# iotpanel.net
KiCad netlist of a schematic drawn in EAGLE
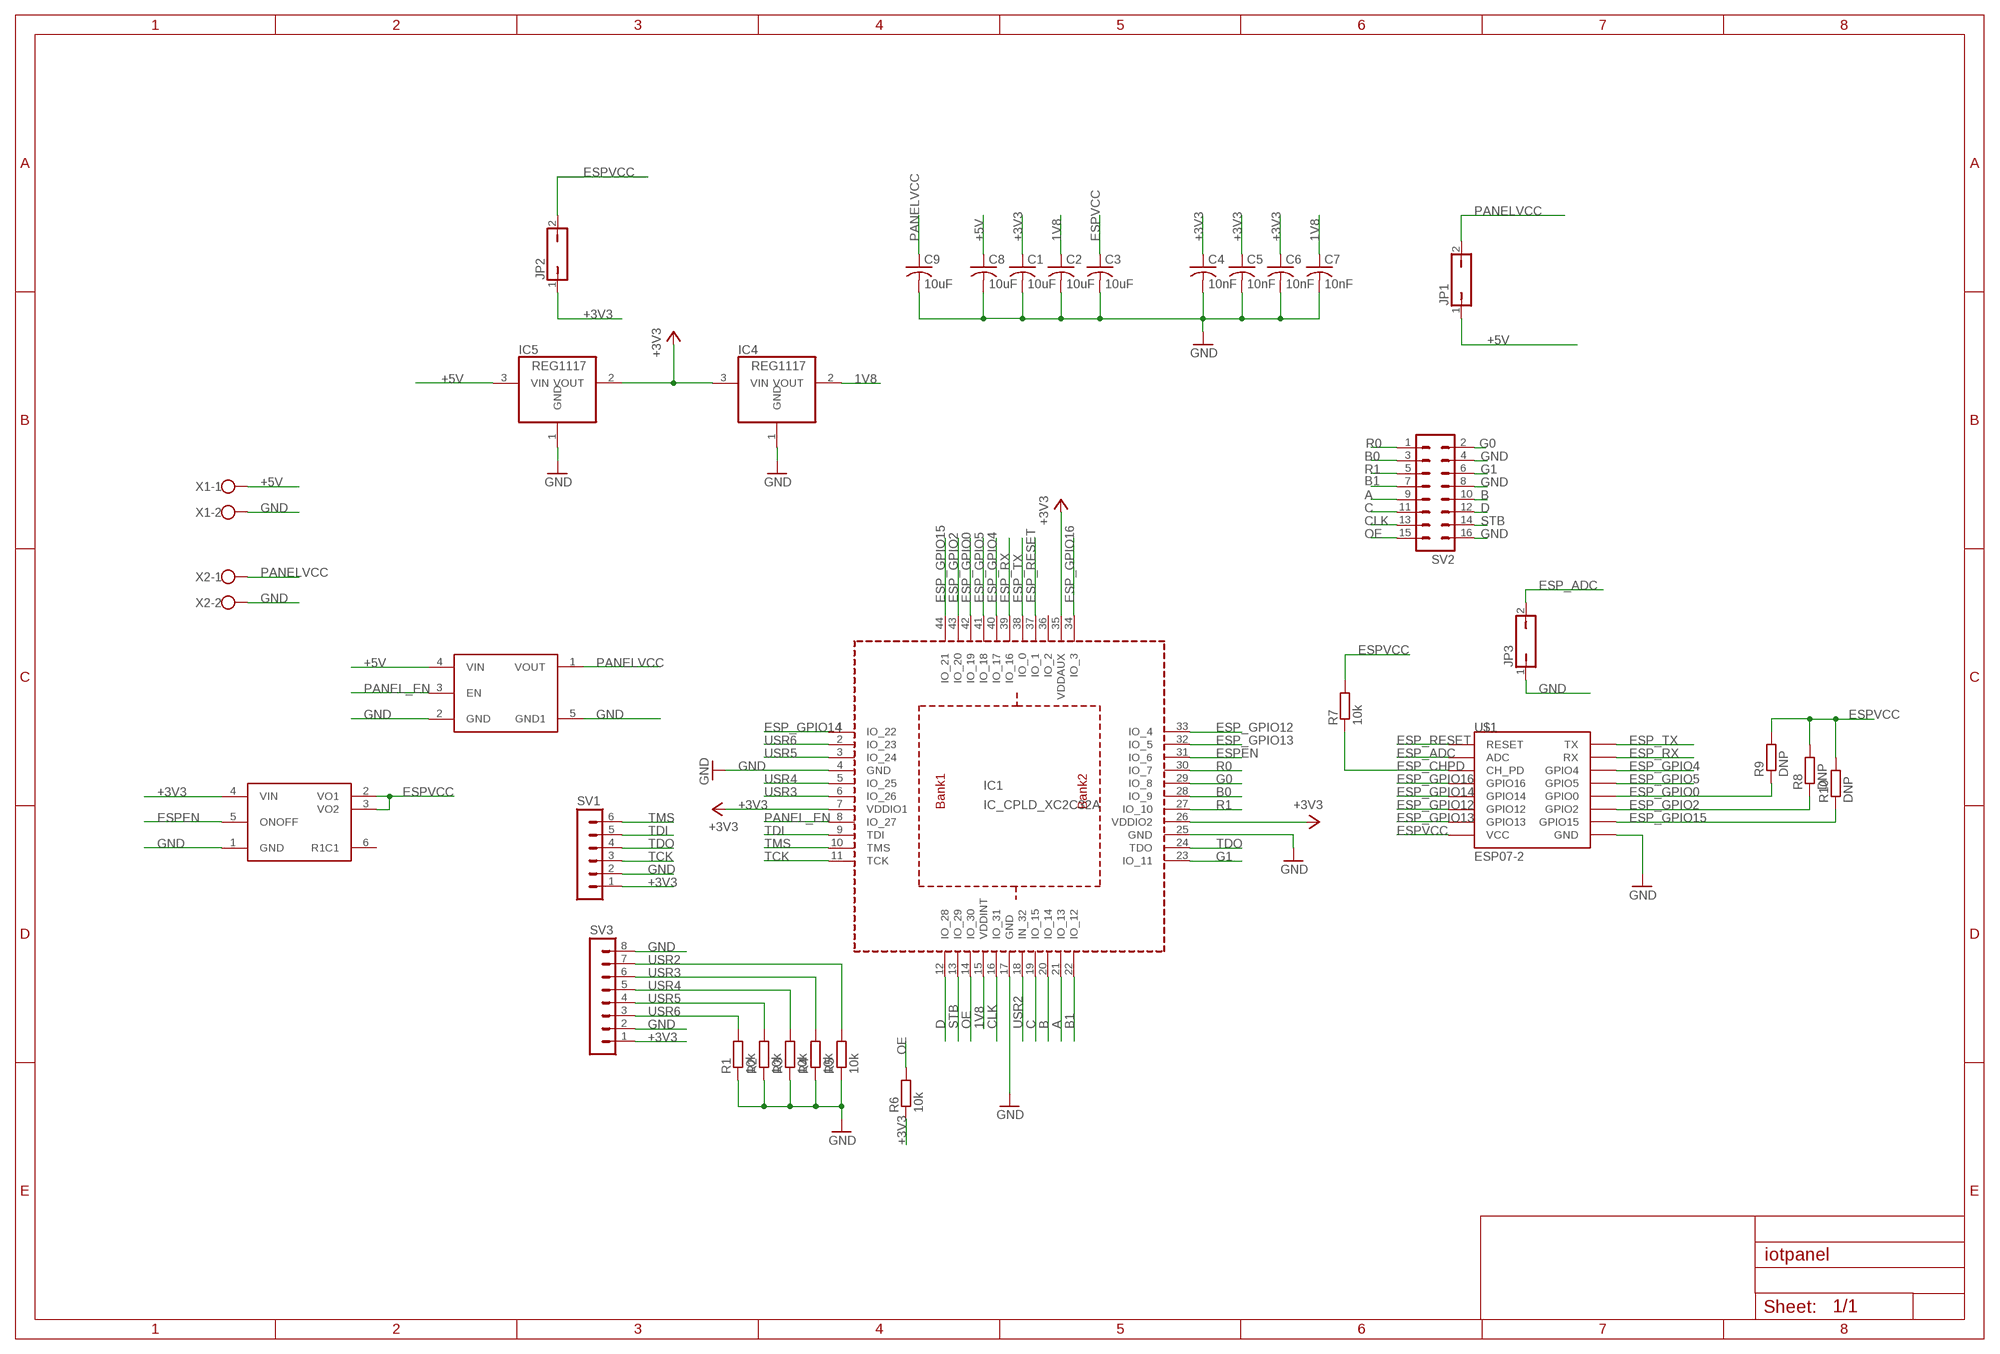
[diagram p0: schematic, sheet 1]

(export (version "E")
  (design (tool "Eeschema 10.0.6"))
  (components
    (comp (ref "C1")
      (value "10uF")
      (footprint "eagle-import:CAPC0805")
      (libsource (lib "eagle-import") (part "CAPACITOR_-0805"))
    )
    (comp (ref "C2")
      (value "10uF")
      (footprint "eagle-import:CAPC0805")
      (libsource (lib "eagle-import") (part "CAPACITOR_-0805"))
    )
    (comp (ref "C3")
      (value "10uF")
      (footprint "eagle-import:CAPC0805")
      (libsource (lib "eagle-import") (part "CAPACITOR_-0805"))
    )
    (comp (ref "C4")
      (value "10nF")
      (footprint "eagle-import:CAPC0805")
      (libsource (lib "eagle-import") (part "CAPACITOR_-0805"))
    )
    (comp (ref "C5")
      (value "10nF")
      (footprint "eagle-import:CAPC0805")
      (libsource (lib "eagle-import") (part "CAPACITOR_-0805"))
    )
    (comp (ref "C6")
      (value "10nF")
      (footprint "eagle-import:CAPC0805")
      (libsource (lib "eagle-import") (part "CAPACITOR_-0805"))
    )
    (comp (ref "C7")
      (value "10nF")
      (footprint "eagle-import:CAPC0805")
      (libsource (lib "eagle-import") (part "CAPACITOR_-0805"))
    )
    (comp (ref "C8")
      (value "10uF")
      (footprint "eagle-import:CAPC0805")
      (libsource (lib "eagle-import") (part "CAPACITOR_-0805"))
    )
    (comp (ref "C9")
      (value "10uF")
      (footprint "eagle-import:CAPC0805")
      (libsource (lib "eagle-import") (part "CAPACITOR_-0805"))
    )
    (comp (ref "IC1")
      (value "IC_CPLD_XC2C32A")
      (footprint "eagle-import:VQ-44")
      (libsource (lib "eagle-import") (part "IC_CPLD_XC2C32A"))
    )
    (comp (ref "IC4")
      (value "REG1117")
      (footprint "eagle-import:SOT223")
      (libsource (lib "eagle-import") (part "REG1117"))
    )
    (comp (ref "IC5")
      (value "REG1117")
      (footprint "eagle-import:SOT223")
      (libsource (lib "eagle-import") (part "REG1117"))
    )
    (comp (ref "JP1")
      (value "JP1Q")
      (footprint "eagle-import:JP1")
      (libsource (lib "eagle-import") (part "JP1Q"))
    )
    (comp (ref "JP2")
      (value "JP1Q")
      (footprint "eagle-import:JP1")
      (libsource (lib "eagle-import") (part "JP1Q"))
    )
    (comp (ref "JP3")
      (value "JP1Q")
      (footprint "eagle-import:JP1")
      (libsource (lib "eagle-import") (part "JP1Q"))
    )
    (comp (ref "R1")
      (value "10k")
      (footprint "eagle-import:R0805")
      (libsource (lib "eagle-import") (part "R-EU_R0805"))
    )
    (comp (ref "R2")
      (value "10k")
      (footprint "eagle-import:R0805")
      (libsource (lib "eagle-import") (part "R-EU_R0805"))
    )
    (comp (ref "R3")
      (value "10k")
      (footprint "eagle-import:R0805")
      (libsource (lib "eagle-import") (part "R-EU_R0805"))
    )
    (comp (ref "R4")
      (value "10k")
      (footprint "eagle-import:R0805")
      (libsource (lib "eagle-import") (part "R-EU_R0805"))
    )
    (comp (ref "R5")
      (value "10k")
      (footprint "eagle-import:R0805")
      (libsource (lib "eagle-import") (part "R-EU_R0805"))
    )
    (comp (ref "R6")
      (value "10k")
      (footprint "eagle-import:R0805")
      (libsource (lib "eagle-import") (part "R-EU_R0805"))
    )
    (comp (ref "R7")
      (value "10k")
      (footprint "eagle-import:R0805")
      (libsource (lib "eagle-import") (part "R-EU_R0805"))
    )
    (comp (ref "R8")
      (value "DNP")
      (footprint "eagle-import:R0805")
      (libsource (lib "eagle-import") (part "R-EU_R0805"))
    )
    (comp (ref "R9")
      (value "DNP")
      (footprint "eagle-import:R0805")
      (libsource (lib "eagle-import") (part "R-EU_R0805"))
    )
    (comp (ref "R10")
      (value "DNP")
      (footprint "eagle-import:R0805")
      (libsource (lib "eagle-import") (part "R-EU_R0805"))
    )
    (comp (ref "SV1")
      (value "MA06-1")
      (footprint "eagle-import:MA06-1")
      (libsource (lib "eagle-import") (part "MA06-1"))
    )
    (comp (ref "SV2")
      (value "ML16")
      (footprint "eagle-import:ML16")
      (fields (field (name "PARTNO") "PRPC004DAAN-RC"))
      (libsource (lib "eagle-import") (part "ML16"))
    )
    (comp (ref "SV3")
      (value "MA08-1")
      (footprint "eagle-import:MA08-1")
      (libsource (lib "eagle-import") (part "MA08-1"))
    )
    (comp (ref "U$1")
      (value "ESP07-2")
      (footprint "eagle-import:ESP07-2")
      (libsource (lib "eagle-import") (part "ESP07-2"))
    )
    (comp (ref "U$2")
      (value "MIC9406XBC6")
      (footprint "eagle-import:SC70-6L")
      (libsource (lib "eagle-import") (part "MIC9406XBC6"))
    )
    (comp (ref "U$3")
      (value "SI1867DL")
      (footprint "eagle-import:SC70-6L")
      (libsource (lib "eagle-import") (part "SI1867DL"))
    )
    (comp (ref "X1")
      (value "W237-102")
      (footprint "eagle-import:W237-102")
      (fields (field (name "MPN") "237-102"))
      (libsource (lib "eagle-import") (part "W237-102"))
    )
    (comp (ref "X2")
      (value "W237-102")
      (footprint "eagle-import:W237-102")
      (fields (field (name "MPN") "237-102"))
      (libsource (lib "eagle-import") (part "W237-102"))
    )
  )
  (nets
    (net (code "1") (name "+3V3") (class "Default")
      (node (ref "C1") (pin "1") (pinfunction "1_1") (pintype "passive"))
      (node (ref "C4") (pin "1") (pinfunction "1_1") (pintype "passive"))
      (node (ref "C5") (pin "1") (pinfunction "1_1") (pintype "passive"))
      (node (ref "C6") (pin "1") (pinfunction "1_1") (pintype "passive"))
      (node (ref "IC1") (pin "26") (pinfunction "VDDIO2_26") (pintype "power_in"))
      (node (ref "IC1") (pin "35") (pinfunction "VDDAUX_35") (pintype "power_in"))
      (node (ref "IC1") (pin "7") (pinfunction "VDDIO1_7") (pintype "power_in"))
      (node (ref "IC4") (pin "3") (pinfunction "VIN_3") (pintype "input"))
      (node (ref "IC5") (pin "2") (pinfunction "VOUT_2") (pintype "output"))
      (node (ref "JP2") (pin "1") (pinfunction "1_1") (pintype "passive"))
      (node (ref "R6") (pin "1") (pinfunction "1_1") (pintype "passive"))
      (node (ref "SV1") (pin "1") (pinfunction "1_1") (pintype "passive"))
      (node (ref "SV3") (pin "1") (pinfunction "1_1") (pintype "passive"))
      (node (ref "U$3") (pin "4") (pinfunction "VIN_4") (pintype "power_in"))
    )
    (net (code "2") (name "/+5V") (class "Default")
      (node (ref "C8") (pin "1") (pinfunction "1_1") (pintype "passive"))
      (node (ref "IC5") (pin "3") (pinfunction "VIN_3") (pintype "input"))
      (node (ref "JP1") (pin "1") (pinfunction "1_1") (pintype "passive"))
      (node (ref "U$2") (pin "4") (pinfunction "VIN_4") (pintype "power_in"))
      (node (ref "X1") (pin "1") (pinfunction "KL_1") (pintype "passive"))
    )
    (net (code "3") (name "/1V8") (class "Default")
      (node (ref "C2") (pin "1") (pinfunction "1_1") (pintype "passive"))
      (node (ref "C7") (pin "1") (pinfunction "1_1") (pintype "passive"))
      (node (ref "IC1") (pin "15") (pinfunction "VDDINT_15") (pintype "power_in"))
      (node (ref "IC4") (pin "2") (pinfunction "VOUT_2") (pintype "output"))
    )
    (net (code "4") (name "/A") (class "Default")
      (node (ref "IC1") (pin "21") (pinfunction "IO_13_21") (pintype "bidirectional"))
      (node (ref "SV2") (pin "9") (pinfunction "9_9") (pintype "passive"))
    )
    (net (code "5") (name "/B") (class "Default")
      (node (ref "IC1") (pin "20") (pinfunction "IO_14_20") (pintype "bidirectional"))
      (node (ref "SV2") (pin "10") (pinfunction "10_10") (pintype "passive"))
    )
    (net (code "6") (name "/B0") (class "Default")
      (node (ref "IC1") (pin "28") (pinfunction "IO_9_28") (pintype "bidirectional"))
      (node (ref "SV2") (pin "3") (pinfunction "3_3") (pintype "passive"))
    )
    (net (code "7") (name "/B1") (class "Default")
      (node (ref "IC1") (pin "22") (pinfunction "IO_12_22") (pintype "bidirectional"))
      (node (ref "SV2") (pin "7") (pinfunction "7_7") (pintype "passive"))
    )
    (net (code "8") (name "/C") (class "Default")
      (node (ref "IC1") (pin "19") (pinfunction "IO_15_19") (pintype "bidirectional"))
      (node (ref "SV2") (pin "11") (pinfunction "11_11") (pintype "passive"))
    )
    (net (code "9") (name "/CLK") (class "Default")
      (node (ref "IC1") (pin "16") (pinfunction "IO_31_16") (pintype "bidirectional"))
      (node (ref "SV2") (pin "13") (pinfunction "13_13") (pintype "passive"))
    )
    (net (code "10") (name "/D") (class "Default")
      (node (ref "IC1") (pin "12") (pinfunction "IO_28_12") (pintype "bidirectional"))
      (node (ref "SV2") (pin "12") (pinfunction "12_12") (pintype "passive"))
    )
    (net (code "11") (name "/ESPEN") (class "Default")
      (node (ref "IC1") (pin "31") (pinfunction "IO_6_31") (pintype "bidirectional"))
      (node (ref "U$3") (pin "5") (pinfunction "ONOFF_5") (pintype "input"))
    )
    (net (code "12") (name "/ESPVCC") (class "Default")
      (node (ref "C3") (pin "1") (pinfunction "1_1") (pintype "passive"))
      (node (ref "JP2") (pin "2") (pinfunction "2_2") (pintype "passive"))
      (node (ref "R10") (pin "2") (pinfunction "2_2") (pintype "passive"))
      (node (ref "R7") (pin "2") (pinfunction "2_2") (pintype "passive"))
      (node (ref "R8") (pin "2") (pinfunction "2_2") (pintype "passive"))
      (node (ref "R9") (pin "2") (pinfunction "2_2") (pintype "passive"))
      (node (ref "U$1") (pin "VCC") (pinfunction "VCC_VCC") (pintype "bidirectional"))
      (node (ref "U$3") (pin "2") (pinfunction "VO1_2") (pintype "power_in"))
      (node (ref "U$3") (pin "3") (pinfunction "VO2_3") (pintype "power_in"))
    )
    (net (code "13") (name "/ESP_ADC") (class "Default")
      (node (ref "JP3") (pin "2") (pinfunction "2_2") (pintype "passive"))
      (node (ref "U$1") (pin "ADC") (pinfunction "ADC_ADC") (pintype "bidirectional"))
    )
    (net (code "14") (name "/ESP_CHPD") (class "Default")
      (node (ref "R7") (pin "1") (pinfunction "1_1") (pintype "passive"))
      (node (ref "U$1") (pin "CH_PD") (pinfunction "CH_PD_CH_PD") (pintype "bidirectional"))
    )
    (net (code "15") (name "/ESP_GPIO0") (class "Default")
      (node (ref "IC1") (pin "42") (pinfunction "IO_19_42") (pintype "bidirectional"))
      (node (ref "R9") (pin "1") (pinfunction "1_1") (pintype "passive"))
      (node (ref "U$1") (pin "GPIO0") (pinfunction "GPIO0_GPIO0") (pintype "bidirectional"))
    )
    (net (code "16") (name "/ESP_GPIO2") (class "Default")
      (node (ref "IC1") (pin "43") (pinfunction "IO_20_43") (pintype "bidirectional"))
      (node (ref "R8") (pin "1") (pinfunction "1_1") (pintype "passive"))
      (node (ref "U$1") (pin "GPIO2") (pinfunction "GPIO2_GPIO2") (pintype "bidirectional"))
    )
    (net (code "17") (name "/ESP_GPIO4") (class "Default")
      (node (ref "IC1") (pin "40") (pinfunction "IO_17_40") (pintype "bidirectional"))
      (node (ref "U$1") (pin "GPIO4") (pinfunction "GPIO4_GPIO4") (pintype "bidirectional"))
    )
    (net (code "18") (name "/ESP_GPIO5") (class "Default")
      (node (ref "IC1") (pin "41") (pinfunction "IO_18_41") (pintype "bidirectional"))
      (node (ref "U$1") (pin "GPIO5") (pinfunction "GPIO5_GPIO5") (pintype "bidirectional"))
    )
    (net (code "19") (name "/ESP_GPIO12") (class "Default")
      (node (ref "IC1") (pin "33") (pinfunction "IO_4_33") (pintype "bidirectional"))
      (node (ref "U$1") (pin "GPIO12") (pinfunction "GPIO12_GPIO12") (pintype "bidirectional"))
    )
    (net (code "20") (name "/ESP_GPIO13") (class "Default")
      (node (ref "IC1") (pin "32") (pinfunction "IO_5_32") (pintype "bidirectional"))
      (node (ref "U$1") (pin "GPIO13") (pinfunction "GPIO13_GPIO13") (pintype "bidirectional"))
    )
    (net (code "21") (name "/ESP_GPIO14") (class "Default")
      (node (ref "IC1") (pin "1") (pinfunction "IO_22_1") (pintype "bidirectional"))
      (node (ref "U$1") (pin "GPIO14") (pinfunction "GPIO14_GPIO14") (pintype "bidirectional"))
    )
    (net (code "22") (name "/ESP_GPIO15") (class "Default")
      (node (ref "IC1") (pin "44") (pinfunction "IO_21_44") (pintype "bidirectional"))
      (node (ref "R10") (pin "1") (pinfunction "1_1") (pintype "passive"))
      (node (ref "U$1") (pin "GPIO15") (pinfunction "GPIO15_GPIO15") (pintype "bidirectional"))
    )
    (net (code "23") (name "/ESP_GPIO16") (class "Default")
      (node (ref "IC1") (pin "34") (pinfunction "IO_3_34") (pintype "bidirectional"))
      (node (ref "U$1") (pin "GPIO16") (pinfunction "GPIO16_GPIO16") (pintype "bidirectional"))
    )
    (net (code "24") (name "/ESP_RESET") (class "Default")
      (node (ref "IC1") (pin "37") (pinfunction "IO_1_37") (pintype "bidirectional"))
      (node (ref "U$1") (pin "REST") (pinfunction "RESET_REST") (pintype "bidirectional"))
    )
    (net (code "25") (name "/ESP_RX") (class "Default")
      (node (ref "IC1") (pin "39") (pinfunction "IO_16_39") (pintype "bidirectional"))
      (node (ref "U$1") (pin "RX") (pinfunction "RX_RX") (pintype "bidirectional"))
    )
    (net (code "26") (name "/ESP_TX") (class "Default")
      (node (ref "IC1") (pin "38") (pinfunction "IO_0_38") (pintype "bidirectional"))
      (node (ref "U$1") (pin "TX") (pinfunction "TX_TX") (pintype "bidirectional"))
    )
    (net (code "27") (name "/G0") (class "Default")
      (node (ref "IC1") (pin "29") (pinfunction "IO_8_29") (pintype "bidirectional"))
      (node (ref "SV2") (pin "2") (pinfunction "2_2") (pintype "passive"))
    )
    (net (code "28") (name "/G1") (class "Default")
      (node (ref "IC1") (pin "23") (pinfunction "IO_11_23") (pintype "bidirectional"))
      (node (ref "SV2") (pin "6") (pinfunction "6_6") (pintype "passive"))
    )
    (net (code "29") (name "/OE") (class "Default")
      (node (ref "IC1") (pin "14") (pinfunction "IO_30_14") (pintype "bidirectional"))
      (node (ref "R6") (pin "2") (pinfunction "2_2") (pintype "passive"))
      (node (ref "SV2") (pin "15") (pinfunction "15_15") (pintype "passive"))
    )
    (net (code "30") (name "/PANELVCC") (class "Default")
      (node (ref "C9") (pin "1") (pinfunction "1_1") (pintype "passive"))
      (node (ref "JP1") (pin "2") (pinfunction "2_2") (pintype "passive"))
      (node (ref "U$2") (pin "1") (pinfunction "VOUT_1") (pintype "power_in"))
      (node (ref "X2") (pin "1") (pinfunction "KL_1") (pintype "passive"))
    )
    (net (code "31") (name "/PANEL_EN") (class "Default")
      (node (ref "IC1") (pin "8") (pinfunction "IO_27_8") (pintype "bidirectional"))
      (node (ref "U$2") (pin "3") (pinfunction "EN_3") (pintype "input"))
    )
    (net (code "32") (name "/R0") (class "Default")
      (node (ref "IC1") (pin "30") (pinfunction "IO_7_30") (pintype "bidirectional"))
      (node (ref "SV2") (pin "1") (pinfunction "1_1") (pintype "passive"))
    )
    (net (code "33") (name "/R1") (class "Default")
      (node (ref "IC1") (pin "27") (pinfunction "IO_10_27") (pintype "bidirectional"))
      (node (ref "SV2") (pin "5") (pinfunction "5_5") (pintype "passive"))
    )
    (net (code "34") (name "/STB") (class "Default")
      (node (ref "IC1") (pin "13") (pinfunction "IO_29_13") (pintype "bidirectional"))
      (node (ref "SV2") (pin "14") (pinfunction "14_14") (pintype "passive"))
    )
    (net (code "35") (name "/TCK") (class "Default")
      (node (ref "IC1") (pin "11") (pinfunction "TCK_11") (pintype "input"))
      (node (ref "SV1") (pin "3") (pinfunction "3_3") (pintype "passive"))
    )
    (net (code "36") (name "/TDI") (class "Default")
      (node (ref "IC1") (pin "9") (pinfunction "TDI_9") (pintype "input"))
      (node (ref "SV1") (pin "5") (pinfunction "5_5") (pintype "passive"))
    )
    (net (code "37") (name "/TDO") (class "Default")
      (node (ref "IC1") (pin "24") (pinfunction "TDO_24") (pintype "output"))
      (node (ref "SV1") (pin "4") (pinfunction "4_4") (pintype "passive"))
    )
    (net (code "38") (name "/TMS") (class "Default")
      (node (ref "IC1") (pin "10") (pinfunction "TMS_10") (pintype "input"))
      (node (ref "SV1") (pin "6") (pinfunction "6_6") (pintype "passive"))
    )
    (net (code "39") (name "/USR2") (class "Default")
      (node (ref "IC1") (pin "18") (pinfunction "IN_32_18") (pintype "input"))
      (node (ref "R5") (pin "2") (pinfunction "2_2") (pintype "passive"))
      (node (ref "SV3") (pin "7") (pinfunction "7_7") (pintype "passive"))
    )
    (net (code "40") (name "/USR3") (class "Default")
      (node (ref "IC1") (pin "6") (pinfunction "IO_26_6") (pintype "bidirectional"))
      (node (ref "R4") (pin "2") (pinfunction "2_2") (pintype "passive"))
      (node (ref "SV3") (pin "6") (pinfunction "6_6") (pintype "passive"))
    )
    (net (code "41") (name "/USR4") (class "Default")
      (node (ref "IC1") (pin "5") (pinfunction "IO_25_5") (pintype "bidirectional"))
      (node (ref "R3") (pin "2") (pinfunction "2_2") (pintype "passive"))
      (node (ref "SV3") (pin "5") (pinfunction "5_5") (pintype "passive"))
    )
    (net (code "42") (name "/USR5") (class "Default")
      (node (ref "IC1") (pin "3") (pinfunction "IO_24_3") (pintype "bidirectional"))
      (node (ref "R2") (pin "2") (pinfunction "2_2") (pintype "passive"))
      (node (ref "SV3") (pin "4") (pinfunction "4_4") (pintype "passive"))
    )
    (net (code "43") (name "/USR6") (class "Default")
      (node (ref "IC1") (pin "2") (pinfunction "IO_23_2") (pintype "bidirectional"))
      (node (ref "R1") (pin "2") (pinfunction "2_2") (pintype "passive"))
      (node (ref "SV3") (pin "3") (pinfunction "3_3") (pintype "passive"))
    )
    (net (code "44") (name "GND") (class "Default")
      (node (ref "C1") (pin "2") (pinfunction "2_2") (pintype "passive"))
      (node (ref "C2") (pin "2") (pinfunction "2_2") (pintype "passive"))
      (node (ref "C3") (pin "2") (pinfunction "2_2") (pintype "passive"))
      (node (ref "C4") (pin "2") (pinfunction "2_2") (pintype "passive"))
      (node (ref "C5") (pin "2") (pinfunction "2_2") (pintype "passive"))
      (node (ref "C6") (pin "2") (pinfunction "2_2") (pintype "passive"))
      (node (ref "C7") (pin "2") (pinfunction "2_2") (pintype "passive"))
      (node (ref "C8") (pin "2") (pinfunction "2_2") (pintype "passive"))
      (node (ref "C9") (pin "2") (pinfunction "2_2") (pintype "passive"))
      (node (ref "IC1") (pin "17") (pinfunction "GND_17") (pintype "power_in"))
      (node (ref "IC1") (pin "25") (pinfunction "GND_25") (pintype "power_in"))
      (node (ref "IC1") (pin "4") (pinfunction "GND_4") (pintype "power_in"))
      (node (ref "IC4") (pin "1") (pinfunction "GND_1") (pintype "power_in"))
      (node (ref "IC5") (pin "1") (pinfunction "GND_1") (pintype "power_in"))
      (node (ref "JP3") (pin "1") (pinfunction "1_1") (pintype "passive"))
      (node (ref "R1") (pin "1") (pinfunction "1_1") (pintype "passive"))
      (node (ref "R2") (pin "1") (pinfunction "1_1") (pintype "passive"))
      (node (ref "R3") (pin "1") (pinfunction "1_1") (pintype "passive"))
      (node (ref "R4") (pin "1") (pinfunction "1_1") (pintype "passive"))
      (node (ref "R5") (pin "1") (pinfunction "1_1") (pintype "passive"))
      (node (ref "SV1") (pin "2") (pinfunction "2_2") (pintype "passive"))
      (node (ref "SV2") (pin "16") (pinfunction "16_16") (pintype "passive"))
      (node (ref "SV2") (pin "4") (pinfunction "4_4") (pintype "passive"))
      (node (ref "SV2") (pin "8") (pinfunction "8_8") (pintype "passive"))
      (node (ref "SV3") (pin "2") (pinfunction "2_2") (pintype "passive"))
      (node (ref "SV3") (pin "8") (pinfunction "8_8") (pintype "passive"))
      (node (ref "U$1") (pin "GND") (pinfunction "GND_GND") (pintype "bidirectional"))
      (node (ref "U$2") (pin "2") (pinfunction "GND_2") (pintype "power_in"))
      (node (ref "U$2") (pin "5") (pinfunction "GND1_5") (pintype "power_in"))
      (node (ref "U$3") (pin "1") (pinfunction "GND_1") (pintype "power_in"))
      (node (ref "X1") (pin "2") (pinfunction "KL_2") (pintype "passive"))
      (node (ref "X2") (pin "2") (pinfunction "KL_2") (pintype "passive"))
    )
    (net (code "45") (name "unconnected-(IC1-IO_2-Pad36)") (class "Default")
      (node (ref "IC1") (pin "36") (pinfunction "IO_2_36") (pintype "bidirectional"))
    )
    (net (code "46") (name "unconnected-(U$3-R1C1-Pad6)") (class "Default")
      (node (ref "U$3") (pin "6") (pinfunction "R1C1_6") (pintype "passive"))
    )
  )
)
